# Microcontroller_07.net
KiCad netlist of a schematic drawn in Altium Designer
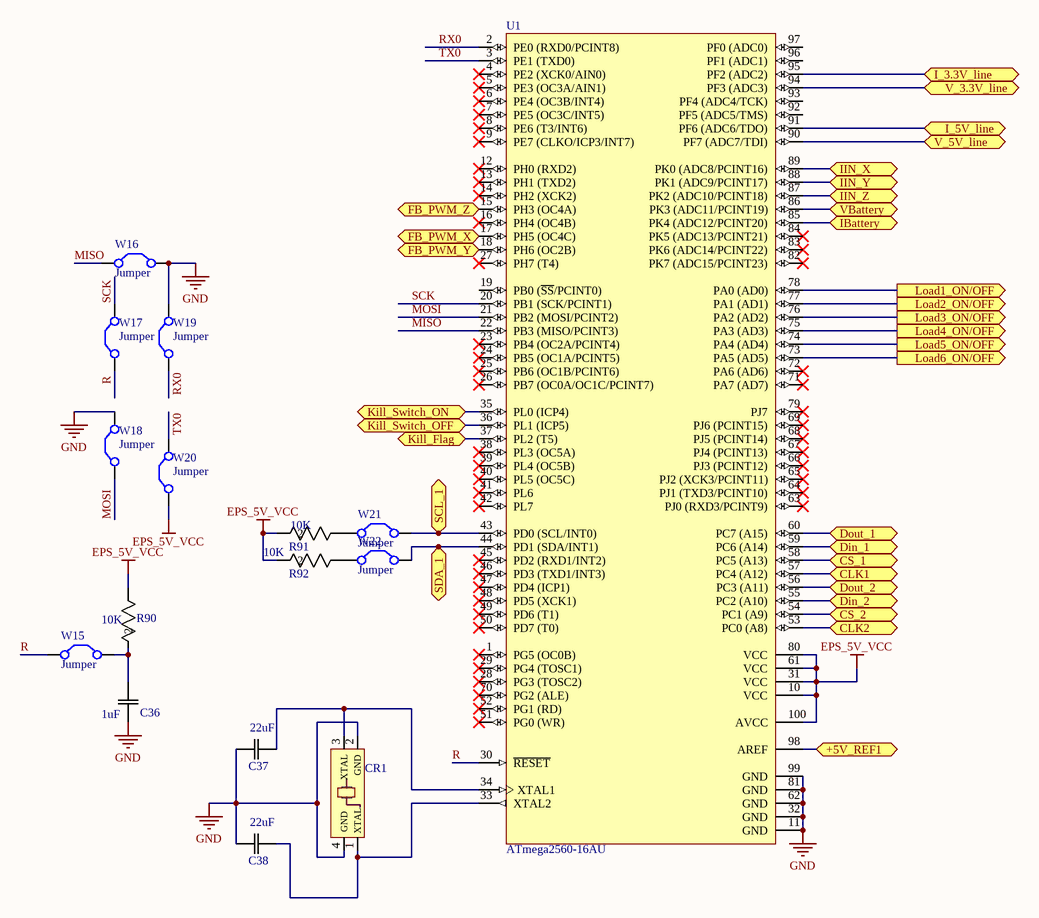
[diagram p0: Microcontroller_07.SchDoc]

(export (version "E")
  (design (tool "Eeschema 10.0.6"))
  (components
    (comp (ref "C36")
      (value "1uF")
      (footprint "0805")
      (description "Ceramic Capacitor 1uF")
      (fields
        (field (name "MANUFACTURER_PART_NUMBER") "GRM155R71H103KA88D")
        (field (name "COPYRIGHT") "Copyright (C) 2015 Accelerated Designs. All rights reserved")
      )
      (libsource (lib "PCDU_Library") (part "GRM155R71H103KA8"))
    )
    (comp (ref "C37")
      (value "22uF")
      (footprint "0805")
      (description "Ceramic Capacitor 22uF")
      (fields
        (field (name "MANUFACTURER_PART_NUMBER") "GRM155R71H103KA88D")
        (field (name "COPYRIGHT") "Copyright (C) 2015 Accelerated Designs. All rights reserved")
      )
      (libsource (lib "PCDU_Library") (part "GRM155R71H103KA8"))
    )
    (comp (ref "C38")
      (value "22uF")
      (footprint "0805")
      (description "Ceramic Capacitor 22uF")
      (fields
        (field (name "MANUFACTURER_PART_NUMBER") "GRM155R71H103KA88D")
        (field (name "COPYRIGHT") "Copyright (C) 2015 Accelerated Designs. All rights reserved")
      )
      (libsource (lib "PCDU_Library") (part "GRM155R71H103KA8"))
    )
    (comp (ref "CR1")
      (value "ABM3B-16.000MHZ")
      (footprint "Crystal")
      (description "CRYSTAL 16.0000MHZ 10PF SMD")
      (libsource (lib "PCDU_Library") (part "ABM3B-16.000MHZ-10-1-U-T"))
    )
    (comp (ref "R90")
      (value "10K")
      (footprint "RC0805N")
      (description "Thick Film Resistors 10k ohm")
      (fields
        (field (name "DIGIKEYPARTNUMBER") "311-4.70KCRTR-ND")
        (field (name "MANUFACTURER_PART_NUMBER") "RC0805FR-074K7L")
        (field (name "COPYRIGHT") "Copyright (C) 2015 Accelerated Designs. All rights reserved")
      )
      (libsource (lib "PCDU_Library") (part "RC0805FR"))
    )
    (comp (ref "R91")
      (value "10K")
      (footprint "RC0805N")
      (description "Thick Film Resistors 10kohm")
      (fields
        (field (name "DIGIKEYPARTNUMBER") "311-4.70KCRTR-ND")
        (field (name "MANUFACTURER_PART_NUMBER") "RC0805FR-074K7L")
        (field (name "COPYRIGHT") "Copyright (C) 2015 Accelerated Designs. All rights reserved")
      )
      (libsource (lib "PCDU_Library") (part "RC0805FR"))
    )
    (comp (ref "R92")
      (value "10K")
      (footprint "RC0805N")
      (description "Thick Film Resistors 10k ohm")
      (fields
        (field (name "DIGIKEYPARTNUMBER") "311-4.70KCRTR-ND")
        (field (name "MANUFACTURER_PART_NUMBER") "RC0805FR-074K7L")
        (field (name "COPYRIGHT") "Copyright (C) 2015 Accelerated Designs. All rights reserved")
      )
      (libsource (lib "PCDU_Library") (part "RC0805FR"))
    )
    (comp (ref "U1")
      (value "ATmega2560-16AU")
      (footprint "100A_M")
      (fields (field (name "PUBLISHER") "Altium Limited"))
      (libsource (lib "EPS_lib") (part "ATmega2560-16AU"))
    )
    (comp (ref "W15")
      (value "Jumper")
      (footprint "PcbLib1:RAD-0.1")
      (description "Jumper Wire")
      (fields (field (name "PUBLISHER") "Altium Limited"))
      (libsource (lib "PCDU_Library") (part "Jumper"))
    )
    (comp (ref "W16")
      (value "Jumper")
      (footprint "PcbLib1:RAD-0.1")
      (description "Jumper Wire")
      (fields (field (name "PUBLISHER") "Altium Limited"))
      (libsource (lib "EPS_lib") (part "Jumper"))
    )
    (comp (ref "W17")
      (value "Jumper")
      (footprint "PcbLib1:RAD-0.1")
      (description "Jumper Wire")
      (fields (field (name "PUBLISHER") "Altium Limited"))
      (libsource (lib "EPS_lib") (part "Jumper"))
    )
    (comp (ref "W18")
      (value "Jumper")
      (footprint "PcbLib1:RAD-0.1")
      (description "Jumper Wire")
      (fields (field (name "PUBLISHER") "Altium Limited"))
      (libsource (lib "EPS_lib") (part "Jumper"))
    )
    (comp (ref "W19")
      (value "Jumper")
      (footprint "PcbLib1:RAD-0.1")
      (description "Jumper Wire")
      (fields (field (name "PUBLISHER") "Altium Limited"))
      (libsource (lib "EPS_lib") (part "Jumper"))
    )
    (comp (ref "W20")
      (value "Jumper")
      (footprint "PcbLib1:RAD-0.1")
      (description "Jumper Wire")
      (fields (field (name "PUBLISHER") "Altium Limited"))
      (libsource (lib "EPS_lib") (part "Jumper"))
    )
    (comp (ref "W21")
      (value "Jumper")
      (footprint "PcbLib1:RAD-0.1")
      (description "Jumper Wire")
      (fields (field (name "PUBLISHER") "Altium Limited"))
      (libsource (lib "PCDU_Library") (part "Jumper"))
    )
    (comp (ref "W22")
      (value "Jumper")
      (footprint "PcbLib1:RAD-0.1")
      (description "Jumper Wire")
      (fields (field (name "PUBLISHER") "Altium Limited"))
      (libsource (lib "PCDU_Library") (part "Jumper"))
    )
  )
  (nets
    (net (code "1") (name "/+5V_REF1") (class "Default")
      (node (ref "U1") (pin "98") (pinfunction "AREF_98") (pintype "power_in"))
    )
    (net (code "2") (name "/CLK1") (class "Default")
      (node (ref "U1") (pin "57") (pinfunction "PC4_(A12)_57") (pintype "bidirectional"))
    )
    (net (code "3") (name "/CLK2") (class "Default")
      (node (ref "U1") (pin "53") (pinfunction "PC0_(A8)_53") (pintype "bidirectional"))
    )
    (net (code "4") (name "/CS_1") (class "Default")
      (node (ref "U1") (pin "58") (pinfunction "PC5_(A13)_58") (pintype "bidirectional"))
    )
    (net (code "5") (name "/CS_2") (class "Default")
      (node (ref "U1") (pin "54") (pinfunction "PC1_(A9)_54") (pintype "bidirectional"))
    )
    (net (code "6") (name "/Din_1") (class "Default")
      (node (ref "U1") (pin "59") (pinfunction "PC6_(A14)_59") (pintype "bidirectional"))
    )
    (net (code "7") (name "/Din_2") (class "Default")
      (node (ref "U1") (pin "55") (pinfunction "PC2_(A10)_55") (pintype "bidirectional"))
    )
    (net (code "8") (name "/Dout_1") (class "Default")
      (node (ref "U1") (pin "60") (pinfunction "PC7_(A15)_60") (pintype "bidirectional"))
    )
    (net (code "9") (name "/Dout_2") (class "Default")
      (node (ref "U1") (pin "56") (pinfunction "PC3_(A11)_56") (pintype "bidirectional"))
    )
    (net (code "10") (name "/FB_PWM_X") (class "Default")
      (node (ref "U1") (pin "17") (pinfunction "PH5_(OC4C)_17") (pintype "bidirectional"))
    )
    (net (code "11") (name "/FB_PWM_Y") (class "Default")
      (node (ref "U1") (pin "18") (pinfunction "PH6_(OC2B)_18") (pintype "bidirectional"))
    )
    (net (code "12") (name "/FB_PWM_Z") (class "Default")
      (node (ref "U1") (pin "15") (pinfunction "PH3_(OC4A)_15") (pintype "bidirectional"))
    )
    (net (code "13") (name "/IBattery") (class "Default")
      (node (ref "U1") (pin "85") (pinfunction "PK4_(ADC12/PCINT20)_85") (pintype "bidirectional"))
    )
    (net (code "14") (name "/IIN_X") (class "Default")
      (node (ref "U1") (pin "89") (pinfunction "PK0_(ADC8/PCINT16)_89") (pintype "bidirectional"))
    )
    (net (code "15") (name "/IIN_Y") (class "Default")
      (node (ref "U1") (pin "88") (pinfunction "PK1_(ADC9/PCINT17)_88") (pintype "bidirectional"))
    )
    (net (code "16") (name "/IIN_Z") (class "Default")
      (node (ref "U1") (pin "87") (pinfunction "PK2_(ADC10/PCINT18)_87") (pintype "bidirectional"))
    )
    (net (code "17") (name "/I_3.3V_line") (class "Default")
      (node (ref "U1") (pin "95") (pinfunction "PF2_(ADC2)_95") (pintype "bidirectional"))
    )
    (net (code "18") (name "/I_5V_line") (class "Default")
      (node (ref "U1") (pin "91") (pinfunction "PF6_(ADC6/TDO)_91") (pintype "bidirectional"))
    )
    (net (code "19") (name "/Kill_Flag") (class "Default")
      (node (ref "U1") (pin "37") (pinfunction "PL2_(T5)_37") (pintype "bidirectional"))
    )
    (net (code "20") (name "/Kill_Switch_OFF") (class "Default")
      (node (ref "U1") (pin "36") (pinfunction "PL1_(ICP5)_36") (pintype "bidirectional"))
    )
    (net (code "21") (name "/Kill_Switch_ON") (class "Default")
      (node (ref "U1") (pin "35") (pinfunction "PL0_(ICP4)_35") (pintype "bidirectional"))
    )
    (net (code "22") (name "/Load1_ON{slash}OFF") (class "Default")
      (node (ref "U1") (pin "78") (pinfunction "PA0_(AD0)_78") (pintype "bidirectional"))
    )
    (net (code "23") (name "/Load2_ON{slash}OFF") (class "Default")
      (node (ref "U1") (pin "77") (pinfunction "PA1_(AD1)_77") (pintype "bidirectional"))
    )
    (net (code "24") (name "/Load3_ON{slash}OFF") (class "Default")
      (node (ref "U1") (pin "76") (pinfunction "PA2_(AD2)_76") (pintype "bidirectional"))
    )
    (net (code "25") (name "/Load4_ON{slash}OFF") (class "Default")
      (node (ref "U1") (pin "75") (pinfunction "PA3_(AD3)_75") (pintype "bidirectional"))
    )
    (net (code "26") (name "/Load5_ON{slash}OFF") (class "Default")
      (node (ref "U1") (pin "74") (pinfunction "PA4_(AD4)_74") (pintype "bidirectional"))
    )
    (net (code "27") (name "/Load6_ON{slash}OFF") (class "Default")
      (node (ref "U1") (pin "73") (pinfunction "PA5_(AD5)_73") (pintype "bidirectional"))
    )
    (net (code "28") (name "/MISO") (class "Default")
      (node (ref "U1") (pin "22") (pinfunction "PB3_(MISO/PCINT3)_22") (pintype "bidirectional"))
      (node (ref "W16") (pin "1") (pinfunction "C1_1") (pintype "passive"))
    )
    (net (code "29") (name "/MOSI") (class "Default")
      (node (ref "U1") (pin "21") (pinfunction "PB2_(MOSI/PCINT2)_21") (pintype "bidirectional"))
      (node (ref "W18") (pin "1") (pinfunction "C1_1") (pintype "passive"))
    )
    (net (code "30") (name "/R") (class "Default")
      (node (ref "U1") (pin "30") (pinfunction "~{RESET}_30") (pintype "input"))
      (node (ref "W15") (pin "1") (pinfunction "C1_1") (pintype "passive"))
      (node (ref "W17") (pin "1") (pinfunction "C1_1") (pintype "passive"))
    )
    (net (code "31") (name "/RX0") (class "Default")
      (node (ref "U1") (pin "2") (pinfunction "PE0_(RXD0/PCINT8)_2") (pintype "bidirectional"))
      (node (ref "W19") (pin "1") (pinfunction "C1_1") (pintype "passive"))
    )
    (net (code "32") (name "/SCK") (class "Default")
      (node (ref "U1") (pin "20") (pinfunction "PB1_(SCK/PCINT1)_20") (pintype "bidirectional"))
      (node (ref "W17") (pin "2") (pinfunction "C2_2") (pintype "passive"))
    )
    (net (code "33") (name "/SCL_1") (class "Default")
      (node (ref "U1") (pin "43") (pinfunction "PD0_(SCL/INT0)_43") (pintype "bidirectional"))
      (node (ref "W21") (pin "2") (pinfunction "C2_2") (pintype "passive"))
    )
    (net (code "34") (name "/SDA_1") (class "Default")
      (node (ref "U1") (pin "44") (pinfunction "PD1_(SDA/INT1)_44") (pintype "bidirectional"))
      (node (ref "W22") (pin "2") (pinfunction "C2_2") (pintype "passive"))
    )
    (net (code "35") (name "/TX0") (class "Default")
      (node (ref "U1") (pin "3") (pinfunction "PE1_(TXD0)_3") (pintype "bidirectional"))
      (node (ref "W20") (pin "2") (pinfunction "C2_2") (pintype "passive"))
    )
    (net (code "36") (name "/VBattery") (class "Default")
      (node (ref "U1") (pin "86") (pinfunction "PK3_(ADC11/PCINT19)_86") (pintype "bidirectional"))
    )
    (net (code "37") (name "/V_3.3V_line") (class "Default")
      (node (ref "U1") (pin "94") (pinfunction "PF3_(ADC3)_94") (pintype "bidirectional"))
    )
    (net (code "38") (name "/V_5V_line") (class "Default")
      (node (ref "U1") (pin "90") (pinfunction "PF7_(ADC7/TDI)_90") (pintype "bidirectional"))
    )
    (net (code "39") (name "EPS_5V_VCC") (class "Default")
      (node (ref "R90") (pin "1") (pinfunction "1_1") (pintype "passive"))
      (node (ref "R91") (pin "2") (pinfunction "2_2") (pintype "passive"))
      (node (ref "R92") (pin "2") (pinfunction "2_2") (pintype "passive"))
      (node (ref "U1") (pin "10") (pinfunction "VCC_10") (pintype "power_in"))
      (node (ref "U1") (pin "100") (pinfunction "AVCC_100") (pintype "power_in"))
      (node (ref "U1") (pin "31") (pinfunction "VCC_31") (pintype "power_in"))
      (node (ref "U1") (pin "61") (pinfunction "VCC_61") (pintype "power_in"))
      (node (ref "U1") (pin "80") (pinfunction "VCC_80") (pintype "power_in"))
      (node (ref "W20") (pin "1") (pinfunction "C1_1") (pintype "passive"))
    )
    (net (code "40") (name "GND") (class "Default")
      (node (ref "C36") (pin "1") (pinfunction "1_1") (pintype "passive"))
      (node (ref "C37") (pin "1") (pinfunction "1_1") (pintype "passive"))
      (node (ref "C38") (pin "1") (pinfunction "1_1") (pintype "passive"))
      (node (ref "CR1") (pin "2") (pinfunction "GND_2") (pintype "passive"))
      (node (ref "CR1") (pin "4") (pinfunction "GND_4") (pintype "passive"))
      (node (ref "U1") (pin "11") (pinfunction "GND_11") (pintype "power_in"))
      (node (ref "U1") (pin "32") (pinfunction "GND_32") (pintype "power_in"))
      (node (ref "U1") (pin "62") (pinfunction "GND_62") (pintype "power_in"))
      (node (ref "U1") (pin "81") (pinfunction "GND_81") (pintype "power_in"))
      (node (ref "U1") (pin "99") (pinfunction "GND_99") (pintype "power_in"))
      (node (ref "W16") (pin "2") (pinfunction "C2_2") (pintype "passive"))
      (node (ref "W18") (pin "2") (pinfunction "C2_2") (pintype "passive"))
      (node (ref "W19") (pin "2") (pinfunction "C2_2") (pintype "passive"))
    )
    (net (code "41") (name "Net-(U1-XTAL1)") (class "Default")
      (node (ref "C37") (pin "2") (pinfunction "2_2") (pintype "passive"))
      (node (ref "CR1") (pin "3") (pinfunction "XTAL_3") (pintype "passive"))
      (node (ref "U1") (pin "34") (pinfunction "XTAL1_34") (pintype "input"))
    )
    (net (code "42") (name "Net-(U1-XTAL2)") (class "Default")
      (node (ref "C38") (pin "2") (pinfunction "2_2") (pintype "passive"))
      (node (ref "CR1") (pin "1") (pinfunction "XTAL_1") (pintype "passive"))
      (node (ref "U1") (pin "33") (pinfunction "XTAL2_33") (pintype "output"))
    )
    (net (code "43") (name "Net-(W15-C2)") (class "Default")
      (node (ref "C36") (pin "2") (pinfunction "2_2") (pintype "passive"))
      (node (ref "R90") (pin "2") (pinfunction "2_2") (pintype "passive"))
      (node (ref "W15") (pin "2") (pinfunction "C2_2") (pintype "passive"))
    )
    (net (code "44") (name "Net-(W21-C1)") (class "Default")
      (node (ref "R91") (pin "1") (pinfunction "1_1") (pintype "passive"))
      (node (ref "W21") (pin "1") (pinfunction "C1_1") (pintype "passive"))
    )
    (net (code "45") (name "Net-(W22-C1)") (class "Default")
      (node (ref "R92") (pin "1") (pinfunction "1_1") (pintype "passive"))
      (node (ref "W22") (pin "1") (pinfunction "C1_1") (pintype "passive"))
    )
    (net (code "46") (name "unconnected-(U1-PA6_(AD6)-Pad72)") (class "Default")
      (node (ref "U1") (pin "72") (pinfunction "PA6_(AD6)_72") (pintype "bidirectional+no_connect"))
    )
    (net (code "47") (name "unconnected-(U1-PA7_(AD7)-Pad71)") (class "Default")
      (node (ref "U1") (pin "71") (pinfunction "PA7_(AD7)_71") (pintype "bidirectional+no_connect"))
    )
    (net (code "48") (name "unconnected-(U1-PB0_(~{SS}{slash}PCINT0)-Pad19)") (class "Default")
      (node (ref "U1") (pin "19") (pinfunction "PB0_(~{SS}/PCINT0)_19") (pintype "bidirectional"))
    )
    (net (code "49") (name "unconnected-(U1-PB4_(OC2A{slash}PCINT4)-Pad23)") (class "Default")
      (node (ref "U1") (pin "23") (pinfunction "PB4_(OC2A/PCINT4)_23") (pintype "bidirectional+no_connect"))
    )
    (net (code "50") (name "unconnected-(U1-PB5_(OC1A{slash}PCINT5)-Pad24)") (class "Default")
      (node (ref "U1") (pin "24") (pinfunction "PB5_(OC1A/PCINT5)_24") (pintype "bidirectional+no_connect"))
    )
    (net (code "51") (name "unconnected-(U1-PB6_(OC1B{slash}PCINT6)-Pad25)") (class "Default")
      (node (ref "U1") (pin "25") (pinfunction "PB6_(OC1B/PCINT6)_25") (pintype "bidirectional+no_connect"))
    )
    (net (code "52") (name "unconnected-(U1-PB7_(OC0A{slash}OC1C{slash}PCINT7)-Pad26)") (class "Default")
      (node (ref "U1") (pin "26") (pinfunction "PB7_(OC0A/OC1C/PCINT7)_26") (pintype "bidirectional+no_connect"))
    )
    (net (code "53") (name "unconnected-(U1-PD2_(RXD1{slash}INT2)-Pad45)") (class "Default")
      (node (ref "U1") (pin "45") (pinfunction "PD2_(RXD1/INT2)_45") (pintype "bidirectional+no_connect"))
    )
    (net (code "54") (name "unconnected-(U1-PD3_(TXD1{slash}INT3)-Pad46)") (class "Default")
      (node (ref "U1") (pin "46") (pinfunction "PD3_(TXD1/INT3)_46") (pintype "bidirectional+no_connect"))
    )
    (net (code "55") (name "unconnected-(U1-PD4_(ICP1)-Pad47)") (class "Default")
      (node (ref "U1") (pin "47") (pinfunction "PD4_(ICP1)_47") (pintype "bidirectional+no_connect"))
    )
    (net (code "56") (name "unconnected-(U1-PD5_(XCK1)-Pad48)") (class "Default")
      (node (ref "U1") (pin "48") (pinfunction "PD5_(XCK1)_48") (pintype "bidirectional+no_connect"))
    )
    (net (code "57") (name "unconnected-(U1-PD6_(T1)-Pad49)") (class "Default")
      (node (ref "U1") (pin "49") (pinfunction "PD6_(T1)_49") (pintype "bidirectional+no_connect"))
    )
    (net (code "58") (name "unconnected-(U1-PD7_(T0)-Pad50)") (class "Default")
      (node (ref "U1") (pin "50") (pinfunction "PD7_(T0)_50") (pintype "bidirectional+no_connect"))
    )
    (net (code "59") (name "unconnected-(U1-PE2_(XCK0{slash}AIN0)-Pad4)") (class "Default")
      (node (ref "U1") (pin "4") (pinfunction "PE2_(XCK0/AIN0)_4") (pintype "bidirectional+no_connect"))
    )
    (net (code "60") (name "unconnected-(U1-PE3_(OC3A{slash}AIN1)-Pad5)") (class "Default")
      (node (ref "U1") (pin "5") (pinfunction "PE3_(OC3A/AIN1)_5") (pintype "bidirectional+no_connect"))
    )
    (net (code "61") (name "unconnected-(U1-PE4_(OC3B{slash}INT4)-Pad6)") (class "Default")
      (node (ref "U1") (pin "6") (pinfunction "PE4_(OC3B/INT4)_6") (pintype "bidirectional+no_connect"))
    )
    (net (code "62") (name "unconnected-(U1-PE5_(OC3C{slash}INT5)-Pad7)") (class "Default")
      (node (ref "U1") (pin "7") (pinfunction "PE5_(OC3C/INT5)_7") (pintype "bidirectional+no_connect"))
    )
    (net (code "63") (name "unconnected-(U1-PE6_(T3{slash}INT6)-Pad8)") (class "Default")
      (node (ref "U1") (pin "8") (pinfunction "PE6_(T3/INT6)_8") (pintype "bidirectional+no_connect"))
    )
    (net (code "64") (name "unconnected-(U1-PE7_(CLKO{slash}ICP3{slash}INT7)-Pad9)") (class "Default")
      (node (ref "U1") (pin "9") (pinfunction "PE7_(CLKO/ICP3/INT7)_9") (pintype "bidirectional+no_connect"))
    )
    (net (code "65") (name "unconnected-(U1-PF0_(ADC0)-Pad97)") (class "Default")
      (node (ref "U1") (pin "97") (pinfunction "PF0_(ADC0)_97") (pintype "bidirectional"))
    )
    (net (code "66") (name "unconnected-(U1-PF1_(ADC1)-Pad96)") (class "Default")
      (node (ref "U1") (pin "96") (pinfunction "PF1_(ADC1)_96") (pintype "bidirectional"))
    )
    (net (code "67") (name "unconnected-(U1-PF4_(ADC4{slash}TCK)-Pad93)") (class "Default")
      (node (ref "U1") (pin "93") (pinfunction "PF4_(ADC4/TCK)_93") (pintype "bidirectional"))
    )
    (net (code "68") (name "unconnected-(U1-PF5_(ADC5{slash}TMS)-Pad92)") (class "Default")
      (node (ref "U1") (pin "92") (pinfunction "PF5_(ADC5/TMS)_92") (pintype "bidirectional"))
    )
    (net (code "69") (name "unconnected-(U1-PG0_(WR)-Pad51)") (class "Default")
      (node (ref "U1") (pin "51") (pinfunction "PG0_(WR)_51") (pintype "bidirectional+no_connect"))
    )
    (net (code "70") (name "unconnected-(U1-PG1_(RD)-Pad52)") (class "Default")
      (node (ref "U1") (pin "52") (pinfunction "PG1_(RD)_52") (pintype "bidirectional+no_connect"))
    )
    (net (code "71") (name "unconnected-(U1-PG2_(ALE)-Pad70)") (class "Default")
      (node (ref "U1") (pin "70") (pinfunction "PG2_(ALE)_70") (pintype "bidirectional+no_connect"))
    )
    (net (code "72") (name "unconnected-(U1-PG3_(TOSC2)-Pad28)") (class "Default")
      (node (ref "U1") (pin "28") (pinfunction "PG3_(TOSC2)_28") (pintype "bidirectional+no_connect"))
    )
    (net (code "73") (name "unconnected-(U1-PG4_(TOSC1)-Pad29)") (class "Default")
      (node (ref "U1") (pin "29") (pinfunction "PG4_(TOSC1)_29") (pintype "bidirectional+no_connect"))
    )
    (net (code "74") (name "unconnected-(U1-PG5_(OC0B)-Pad1)") (class "Default")
      (node (ref "U1") (pin "1") (pinfunction "PG5_(OC0B)_1") (pintype "bidirectional+no_connect"))
    )
    (net (code "75") (name "unconnected-(U1-PH0_(RXD2)-Pad12)") (class "Default")
      (node (ref "U1") (pin "12") (pinfunction "PH0_(RXD2)_12") (pintype "bidirectional+no_connect"))
    )
    (net (code "76") (name "unconnected-(U1-PH1_(TXD2)-Pad13)") (class "Default")
      (node (ref "U1") (pin "13") (pinfunction "PH1_(TXD2)_13") (pintype "bidirectional+no_connect"))
    )
    (net (code "77") (name "unconnected-(U1-PH2_(XCK2)-Pad14)") (class "Default")
      (node (ref "U1") (pin "14") (pinfunction "PH2_(XCK2)_14") (pintype "bidirectional+no_connect"))
    )
    (net (code "78") (name "unconnected-(U1-PH4_(OC4B)-Pad16)") (class "Default")
      (node (ref "U1") (pin "16") (pinfunction "PH4_(OC4B)_16") (pintype "bidirectional+no_connect"))
    )
    (net (code "79") (name "unconnected-(U1-PH7_(T4)-Pad27)") (class "Default")
      (node (ref "U1") (pin "27") (pinfunction "PH7_(T4)_27") (pintype "bidirectional+no_connect"))
    )
    (net (code "80") (name "unconnected-(U1-PJ0_(RXD3{slash}PCINT9)-Pad63)") (class "Default")
      (node (ref "U1") (pin "63") (pinfunction "PJ0_(RXD3/PCINT9)_63") (pintype "bidirectional+no_connect"))
    )
    (net (code "81") (name "unconnected-(U1-PJ1_(TXD3{slash}PCINT10)-Pad64)") (class "Default")
      (node (ref "U1") (pin "64") (pinfunction "PJ1_(TXD3/PCINT10)_64") (pintype "bidirectional+no_connect"))
    )
    (net (code "82") (name "unconnected-(U1-PJ2_(XCK3{slash}PCINT11)-Pad65)") (class "Default")
      (node (ref "U1") (pin "65") (pinfunction "PJ2_(XCK3/PCINT11)_65") (pintype "bidirectional+no_connect"))
    )
    (net (code "83") (name "unconnected-(U1-PJ3_(PCINT12)-Pad66)") (class "Default")
      (node (ref "U1") (pin "66") (pinfunction "PJ3_(PCINT12)_66") (pintype "bidirectional+no_connect"))
    )
    (net (code "84") (name "unconnected-(U1-PJ4_(PCINT13)-Pad67)") (class "Default")
      (node (ref "U1") (pin "67") (pinfunction "PJ4_(PCINT13)_67") (pintype "bidirectional+no_connect"))
    )
    (net (code "85") (name "unconnected-(U1-PJ5_(PCINT14)-Pad68)") (class "Default")
      (node (ref "U1") (pin "68") (pinfunction "PJ5_(PCINT14)_68") (pintype "bidirectional+no_connect"))
    )
    (net (code "86") (name "unconnected-(U1-PJ6_(PCINT15)-Pad69)") (class "Default")
      (node (ref "U1") (pin "69") (pinfunction "PJ6_(PCINT15)_69") (pintype "bidirectional+no_connect"))
    )
    (net (code "87") (name "unconnected-(U1-PJ7-Pad79)") (class "Default")
      (node (ref "U1") (pin "79") (pinfunction "PJ7_79") (pintype "bidirectional+no_connect"))
    )
    (net (code "88") (name "unconnected-(U1-PK5_(ADC13{slash}PCINT21)-Pad84)") (class "Default")
      (node (ref "U1") (pin "84") (pinfunction "PK5_(ADC13/PCINT21)_84") (pintype "bidirectional+no_connect"))
    )
    (net (code "89") (name "unconnected-(U1-PK6_(ADC14{slash}PCINT22)-Pad83)") (class "Default")
      (node (ref "U1") (pin "83") (pinfunction "PK6_(ADC14/PCINT22)_83") (pintype "bidirectional+no_connect"))
    )
    (net (code "90") (name "unconnected-(U1-PK7_(ADC15{slash}PCINT23)-Pad82)") (class "Default")
      (node (ref "U1") (pin "82") (pinfunction "PK7_(ADC15/PCINT23)_82") (pintype "bidirectional+no_connect"))
    )
    (net (code "91") (name "unconnected-(U1-PL3_(OC5A)-Pad38)") (class "Default")
      (node (ref "U1") (pin "38") (pinfunction "PL3_(OC5A)_38") (pintype "bidirectional+no_connect"))
    )
    (net (code "92") (name "unconnected-(U1-PL4_(OC5B)-Pad39)") (class "Default")
      (node (ref "U1") (pin "39") (pinfunction "PL4_(OC5B)_39") (pintype "bidirectional+no_connect"))
    )
    (net (code "93") (name "unconnected-(U1-PL5_(OC5C)-Pad40)") (class "Default")
      (node (ref "U1") (pin "40") (pinfunction "PL5_(OC5C)_40") (pintype "bidirectional+no_connect"))
    )
    (net (code "94") (name "unconnected-(U1-PL6-Pad41)") (class "Default")
      (node (ref "U1") (pin "41") (pinfunction "PL6_41") (pintype "bidirectional+no_connect"))
    )
    (net (code "95") (name "unconnected-(U1-PL7-Pad42)") (class "Default")
      (node (ref "U1") (pin "42") (pinfunction "PL7_42") (pintype "bidirectional+no_connect"))
    )
  )
)
